# UVandLight_I2C_V3.net
KiCad netlist of a schematic drawn in EAGLE
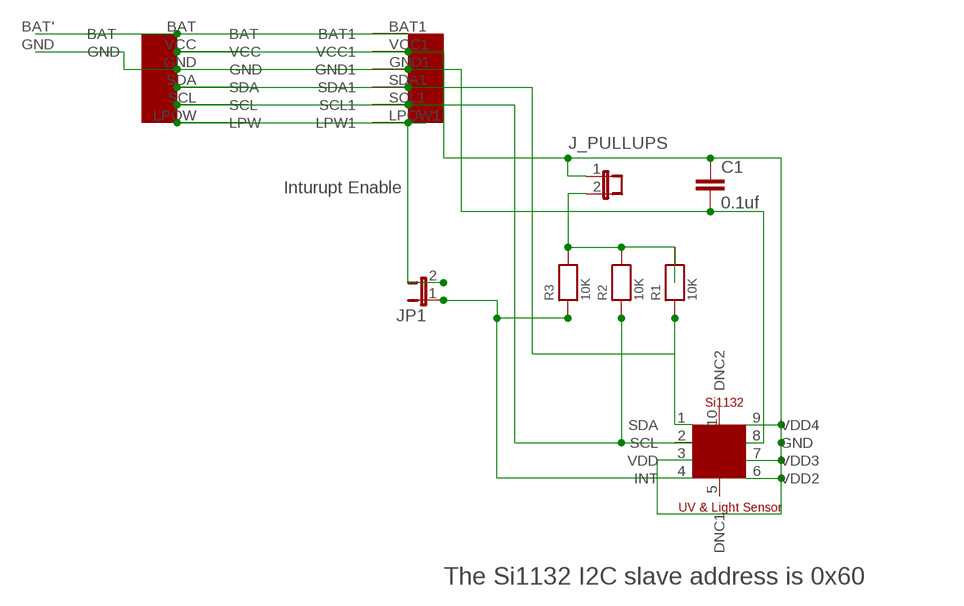
[diagram p0: schematic, sheet 1]

(export (version "E")
  (design (tool "Eeschema 10.0.6"))
  (components
    (comp (ref "C1")
      (value "0.1uf")
      (footprint "eagle-import:0402-CAP")
      (libsource (lib "eagle-import") (part "CAP0402-CAP"))
    )
    (comp (ref "JP1")
      (value "JUMPER-2SMD-NO-NS")
      (footprint "eagle-import:SJ_2S-NO-NS")
      (libsource (lib "eagle-import") (part "JUMPER-2SMD-NO-NS"))
    )
    (comp (ref "J_PULLUPS")
      (value "JUMPER-2PAD")
      (footprint "eagle-import:JUMPER-2PAD")
      (libsource (lib "eagle-import") (part "JUMPER-2PAD"))
    )
    (comp (ref "R1")
      (value "10K")
      (footprint "eagle-import:0402")
      (libsource (lib "eagle-import") (part "RESISTOR0402"))
    )
    (comp (ref "R2")
      (value "10K")
      (footprint "eagle-import:0402")
      (libsource (lib "eagle-import") (part "RESISTOR0402"))
    )
    (comp (ref "R3")
      (value "10K")
      (footprint "eagle-import:0402")
      (libsource (lib "eagle-import") (part "RESISTOR0402"))
    )
    (comp (ref "U$1")
      (value "EZ-I2CHEADERV1")
      (footprint "eagle-import:EZ-I2CHEADERV1")
      (libsource (lib "eagle-import") (part "EZ-I2CHEADERV1"))
    )
    (comp (ref "U$2")
      (value "UV-SI1132")
      (footprint "eagle-import:UV-SI1132")
      (libsource (lib "eagle-import") (part "UV-SI1132"))
    )
    (comp (ref "U$4")
      (value "MINI_BATTERY_HOLES")
      (footprint "eagle-import:MINI_BATTERY_HOLES")
      (libsource (lib "eagle-import") (part "MINI_BATTERY_HOLES"))
    )
  )
  (nets
    (net (code "1") (name "Net-(J_PULLUPS-Pad2)") (class "Default")
      (node (ref "J_PULLUPS") (pin "2") (pinfunction "2_2") (pintype "passive"))
      (node (ref "R1") (pin "2") (pinfunction "2_2") (pintype "passive"))
      (node (ref "R2") (pin "2") (pinfunction "2_2") (pintype "passive"))
      (node (ref "R3") (pin "2") (pinfunction "2_2") (pintype "passive"))
    )
    (net (code "2") (name "Net-(U$1-LPW)") (class "Default")
      (node (ref "JP1") (pin "2") (pinfunction "2_2") (pintype "passive"))
      (node (ref "U$1") (pin "LPOW") (pinfunction "LPW_LPOW") (pintype "bidirectional"))
      (node (ref "U$1") (pin "LPOW1") (pinfunction "LPW1_LPOW1") (pintype "bidirectional"))
    )
    (net (code "3") (name "Net-(U$2-GND)") (class "Default")
      (node (ref "C1") (pin "2") (pinfunction "2_2") (pintype "passive"))
      (node (ref "U$1") (pin "GND") (pinfunction "GND_GND") (pintype "bidirectional"))
      (node (ref "U$1") (pin "GND1") (pinfunction "GND1_GND1") (pintype "bidirectional"))
      (node (ref "U$2") (pin "8") (pinfunction "GND_8") (pintype "bidirectional"))
      (node (ref "U$4") (pin "GND") (pinfunction "GND_GND") (pintype "bidirectional"))
    )
    (net (code "4") (name "Net-(U$2-INT)") (class "Default")
      (node (ref "JP1") (pin "1") (pinfunction "1_1") (pintype "passive"))
      (node (ref "R3") (pin "1") (pinfunction "1_1") (pintype "passive"))
      (node (ref "U$2") (pin "4") (pinfunction "INT_4") (pintype "bidirectional"))
    )
    (net (code "5") (name "Net-(U$2-SCL)") (class "Default")
      (node (ref "R2") (pin "1") (pinfunction "1_1") (pintype "passive"))
      (node (ref "U$1") (pin "SCL") (pinfunction "SCL_SCL") (pintype "bidirectional"))
      (node (ref "U$1") (pin "SCL1") (pinfunction "SCL1_SCL1") (pintype "bidirectional"))
      (node (ref "U$2") (pin "2") (pinfunction "SCL_2") (pintype "bidirectional"))
    )
    (net (code "6") (name "Net-(U$2-SDA)") (class "Default")
      (node (ref "R1") (pin "1") (pinfunction "1_1") (pintype "passive"))
      (node (ref "U$1") (pin "SDA") (pinfunction "SDA_SDA") (pintype "bidirectional"))
      (node (ref "U$1") (pin "SDA1") (pinfunction "SDA1_SDA1") (pintype "bidirectional"))
      (node (ref "U$2") (pin "1") (pinfunction "SDA_1") (pintype "bidirectional"))
    )
    (net (code "7") (name "Net-(U$2-VDD)") (class "Default")
      (node (ref "C1") (pin "1") (pinfunction "1_1") (pintype "passive"))
      (node (ref "J_PULLUPS") (pin "1") (pinfunction "1_1") (pintype "passive"))
      (node (ref "U$1") (pin "VCC") (pinfunction "VCC_VCC") (pintype "bidirectional"))
      (node (ref "U$1") (pin "VCC1") (pinfunction "VCC1_VCC1") (pintype "bidirectional"))
      (node (ref "U$2") (pin "3") (pinfunction "VDD_3") (pintype "bidirectional"))
      (node (ref "U$2") (pin "6") (pinfunction "VDD2_6") (pintype "bidirectional"))
      (node (ref "U$2") (pin "7") (pinfunction "VDD3_7") (pintype "bidirectional"))
      (node (ref "U$2") (pin "9") (pinfunction "VDD4_9") (pintype "bidirectional"))
    )
    (net (code "8") (name "Net-(U$4-BAT)") (class "Default")
      (node (ref "U$1") (pin "BAT") (pinfunction "BAT_BAT") (pintype "bidirectional"))
      (node (ref "U$1") (pin "BAT1") (pinfunction "BAT1_BAT1") (pintype "bidirectional"))
      (node (ref "U$4") (pin "BAT'") (pinfunction "BAT_BAT'") (pintype "bidirectional"))
    )
    (net (code "9") (name "unconnected-(U$2-DNC1-Pad5)") (class "Default")
      (node (ref "U$2") (pin "5") (pinfunction "DNC1_5") (pintype "bidirectional"))
    )
    (net (code "10") (name "unconnected-(U$2-DNC2-Pad10)") (class "Default")
      (node (ref "U$2") (pin "10") (pinfunction "DNC2_10") (pintype "bidirectional"))
    )
  )
)
